# Dev_BRD_STM32F103C8T6.net
KiCad netlist of a schematic drawn in Altium Designer
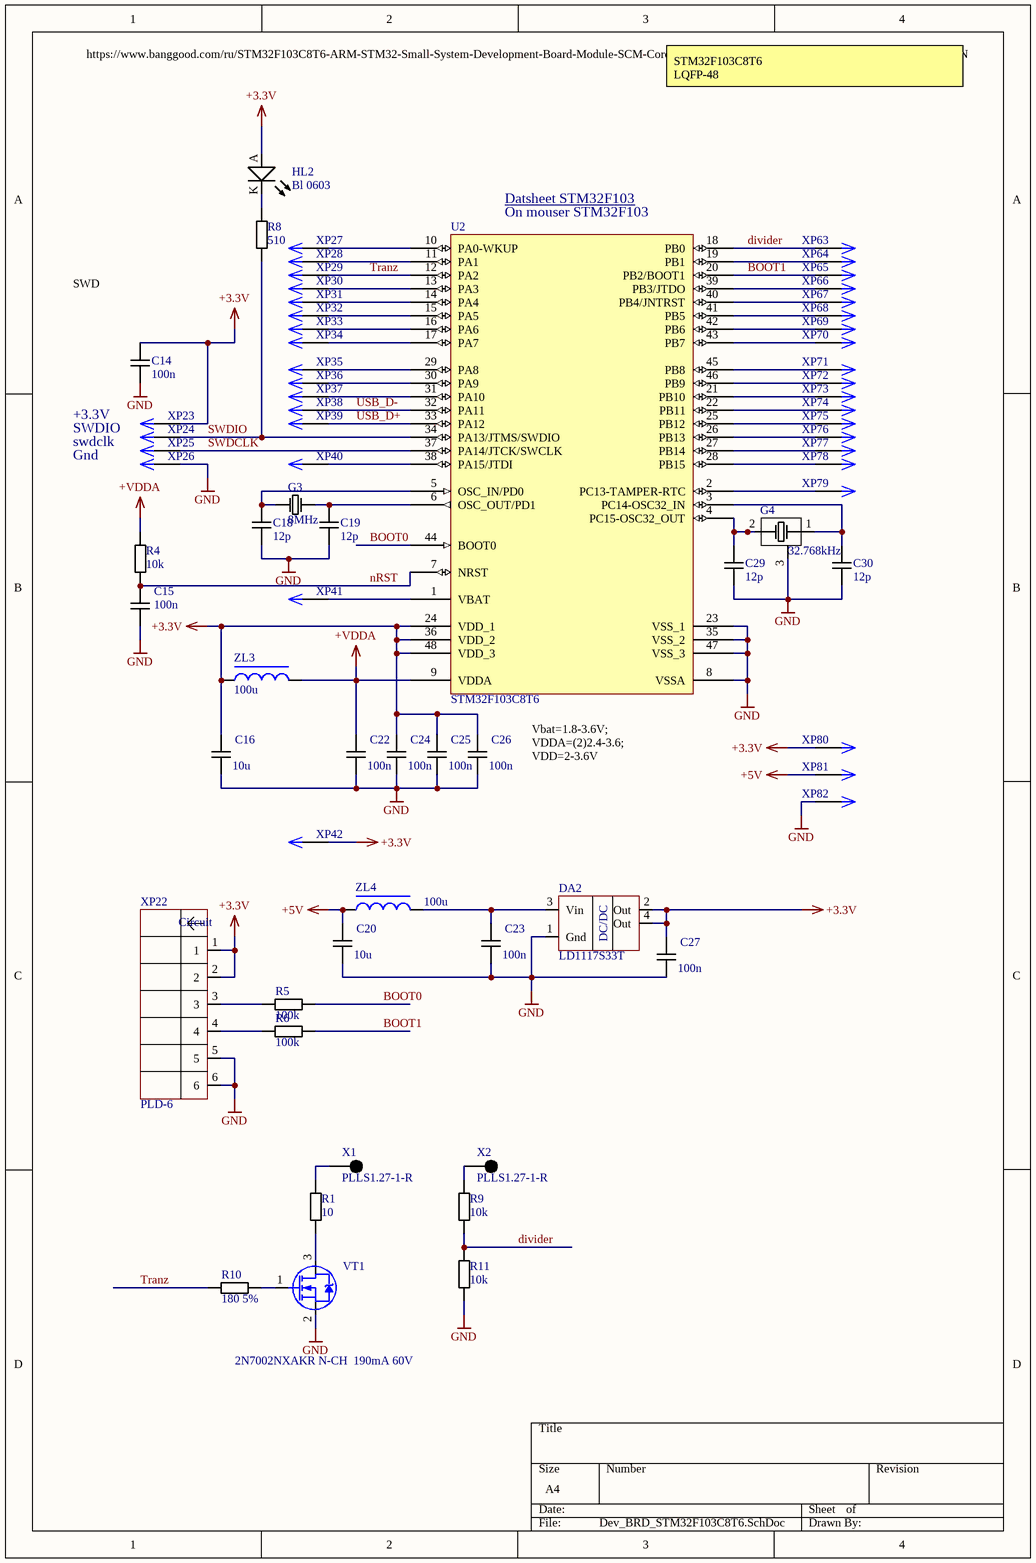
[diagram p0: Dev_BRD_STM32F103C8T6.SchDoc]

(export (version "E")
  (design (tool "Eeschema 10.0.6"))
  (components
    (comp (ref "C14")
      (value "100n")
      (footprint "CAPC1608(0603)N")
      (description "?")
      (fields (field (name "PART NUMBER") "CAPC1608(0603)"))
      (libsource (lib "SssAccesDatbase") (part "Cap"))
    )
    (comp (ref "C15")
      (value "100n")
      (footprint "CAPC1608(0603)N")
      (description "?")
      (fields (field (name "PART NUMBER") "CAPC1608(0603)"))
      (libsource (lib "SssAccesDatbase") (part "Cap"))
    )
    (comp (ref "C16")
      (value "10u")
      (footprint "CAPC1608(0603)N")
      (description "?")
      (fields (field (name "PART NUMBER") "CAPC1608(0603)"))
      (libsource (lib "SssAccesDatbase") (part "Cap"))
    )
    (comp (ref "C18")
      (value "12p")
      (footprint "CAPC1608(0603)N")
      (description "?")
      (fields (field (name "PART NUMBER") "CAPC1608(0603)"))
      (libsource (lib "SssAccesDatbase") (part "Cap"))
    )
    (comp (ref "C19")
      (value "12p")
      (footprint "CAPC1608(0603)N")
      (description "?")
      (fields (field (name "PART NUMBER") "CAPC1608(0603)"))
      (libsource (lib "SssAccesDatbase") (part "Cap"))
    )
    (comp (ref "C20")
      (value "10u")
      (footprint "CAPC1608(0603)N")
      (description "?")
      (fields (field (name "PART NUMBER") "CAPC1608(0603)"))
      (libsource (lib "SssAccesDatbase") (part "Cap"))
    )
    (comp (ref "C22")
      (value "100n")
      (footprint "CAPC1608(0603)N")
      (description "?")
      (fields (field (name "PART NUMBER") "CAPC1608(0603)"))
      (libsource (lib "SssAccesDatbase") (part "Cap"))
    )
    (comp (ref "C23")
      (value "100n")
      (footprint "CAPC1608(0603)N")
      (description "?")
      (fields (field (name "PART NUMBER") "CAPC1608(0603)"))
      (libsource (lib "SssAccesDatbase") (part "Cap"))
    )
    (comp (ref "C24")
      (value "100n")
      (footprint "CAPC1608(0603)N")
      (description "?")
      (fields (field (name "PART NUMBER") "CAPC1608(0603)"))
      (libsource (lib "SssAccesDatbase") (part "Cap"))
    )
    (comp (ref "C25")
      (value "100n")
      (footprint "CAPC1608(0603)N")
      (description "?")
      (fields (field (name "PART NUMBER") "CAPC1608(0603)"))
      (libsource (lib "SssAccesDatbase") (part "Cap"))
    )
    (comp (ref "C26")
      (value "100n")
      (footprint "CAPC1608(0603)N")
      (description "?")
      (fields (field (name "PART NUMBER") "CAPC1608(0603)"))
      (libsource (lib "SssAccesDatbase") (part "Cap"))
    )
    (comp (ref "C27")
      (value "100n")
      (footprint "CAPC1608(0603)N")
      (description "?")
      (fields (field (name "PART NUMBER") "CAPC1608(0603)"))
      (libsource (lib "SssAccesDatbase") (part "Cap"))
    )
    (comp (ref "C29")
      (value "12p")
      (footprint "CAPC1608(0603)N")
      (description "?")
      (fields (field (name "PART NUMBER") "CAPC1608(0603)"))
      (libsource (lib "SssAccesDatbase") (part "Cap"))
    )
    (comp (ref "C30")
      (value "12p")
      (footprint "CAPC1608(0603)N")
      (description "?")
      (fields (field (name "PART NUMBER") "CAPC1608(0603)"))
      (libsource (lib "SssAccesDatbase") (part "Cap"))
    )
    (comp (ref "DA2")
      (value "LD1117S33T")
      (footprint "SOT223_M")
      (description "LDO Voltage Regulators 3.3V 0.8A Positive")
      (fields (field (name "DIGI-KEY PART NUMBER") "?"))
      (libsource (lib "SssAccesDatbase") (part "LD1117S33T"))
    )
    (comp (ref "G3")
      (value "8MHz")
      (footprint "HC-49/S")
      (description "Crystal HC-49/S")
      (libsource (lib "SssAccesDatbase") (part "Crystal"))
    )
    (comp (ref "G4")
      (value "32.768kHz")
      (footprint "CRYSTAL_CMR309T")
      (description "Crystals 32.768KHz")
      (fields
        (field (name "PART NUMBER") "AB26T-32.768KHZ")
        (field (name "MOUSER PART NUMBER") "815-AB26T-32.768KHZ")
      )
      (libsource (lib "SssAccesDatbase") (part "Crystal 3 pin"))
    )
    (comp (ref "HL2")
      (value "Bl 0603")
      (footprint "LED-0603-BLUE")
      (description "LED BLUE DIFFUSED 0603 SMD")
      (fields
        (field (name "PART NUMBER") "150060BS55040")
        (field (name "DIGI-KEY PART NUMBER") "732-12013-1-ND")
      )
      (libsource (lib "SssAccesDatbase") (part "LED"))
    )
    (comp (ref "R1")
      (value "10")
      (footprint "REZKemet 0402")
      (description "RES SMD 0402 180 5% 100ppm")
      (fields
        (field (name "PART NUMBER") "RMCF0402JT180R")
        (field (name "DIGI-KEY PART NUMBER") "RMCF0402JT180RCT-ND")
      )
      (libsource (lib "") (part "Resistor general_1"))
    )
    (comp (ref "R4")
      (value "10k")
      (footprint "RESC1608(0603)N")
      (fields (field (name "PART NUMBER") "RESC1608(0603)") (field (name "DIGI-KEY PART NUMBER") "???"))
      (libsource (lib "") (part "Resistor general_1"))
    )
    (comp (ref "R5")
      (value "100k")
      (footprint "RESC1608(0603)N")
      (fields (field (name "PART NUMBER") "RESC1608(0603)") (field (name "DIGI-KEY PART NUMBER") "???"))
      (libsource (lib "SssAccesDatbase") (part "Resistor general"))
    )
    (comp (ref "R6")
      (value "100k")
      (footprint "RESC1608(0603)N")
      (fields (field (name "PART NUMBER") "RESC1608(0603)") (field (name "DIGI-KEY PART NUMBER") "???"))
      (libsource (lib "SssAccesDatbase") (part "Resistor general"))
    )
    (comp (ref "R8")
      (value "510")
      (footprint "RESC1608(0603)N")
      (fields (field (name "PART NUMBER") "RESC1608(0603)") (field (name "DIGI-KEY PART NUMBER") "???"))
      (libsource (lib "") (part "Resistor general_3"))
    )
    (comp (ref "R9")
      (value "10k")
      (footprint "RESC1608(0603)N")
      (fields (field (name "PART NUMBER") "RESC1608(0603)") (field (name "DIGI-KEY PART NUMBER") "???"))
      (libsource (lib "") (part "Resistor general_1"))
    )
    (comp (ref "R10")
      (value "180 5%")
      (footprint "REZKemet 0402")
      (description "RES SMD 0402 180 5% 100ppm")
      (fields
        (field (name "PART NUMBER") "RMCF0402JT180R")
        (field (name "DIGI-KEY PART NUMBER") "RMCF0402JT180RCT-ND")
      )
      (libsource (lib "") (part "Resistor general_2"))
    )
    (comp (ref "R11")
      (value "10k")
      (footprint "RESC1608(0603)N")
      (fields (field (name "PART NUMBER") "RESC1608(0603)") (field (name "DIGI-KEY PART NUMBER") "???"))
      (libsource (lib "") (part "Resistor general_1"))
    )
    (comp (ref "U2")
      (value "STM32F103C8T6")
      (footprint "LQFP48_L")
      (description "ARM Microcontrollers - MCU 32BIT Cortex M3 64KB 20KB RAM 2X12 ADC")
      (fields
        (field (name "MOUSER PART NUMBER") "511-STM32F103C8T6")
        (field (name "PUBLISHER") "Altium Limited")
      )
      (libsource (lib "SssAccesDatbase") (part "STM32F103C8T6"))
    )
    (comp (ref "VT1")
      (value "2N7002NXAKR N-CH  190mА 60V")
      (footprint "SOT23-3N")
      (description "N-Channel 60V 190mA (Ta), 300mA (Tc) 265mW (Ta), 1.33W (Tc) Surface Mount TO-236AB")
      (fields
        (field (name "PART NUMBER") "2N7002NXAKR")
        (field (name "DIGI-KEY PART NUMBER") "1727-8643-1-ND")
      )
      (libsource (lib "SssAccesDatbase") (part "N-CH_MOSFET_GSD"))
    )
    (comp (ref "X1")
      (value "PLLS1.27-1-R")
      (footprint "PLLS1.27-1-R")
      (libsource (lib "SssAccesDatbase") (part "X1_1"))
    )
    (comp (ref "X2")
      (value "PLLS1.27-1-R")
      (footprint "PLLS1.27-1-R")
      (libsource (lib "SssAccesDatbase") (part "X1_1"))
    )
    (comp (ref "XP22")
      (value "PLD-6")
      (footprint "PLD-6-3D")
      (libsource (lib "SssAccesDatbase") (part "XP-6"))
    )
    (comp (ref "XP23")
      (value "PLS-1")
      (footprint "PLS-1-3D")
      (description "CONN HEADER VERT 1POS")
      (fields
        (field (name "DIGI-KEY PART NUMBER") "S1011EC-01-ND")
        (field (name "MANUFACTURER PART NUMBER") "PRPC001SAAN-RC")
      )
      (libsource (lib "SssAccesDatbase") (part "XP-1_1"))
    )
    (comp (ref "XP24")
      (value "PLS-1")
      (footprint "PLS-1-3D")
      (description "CONN HEADER VERT 1POS")
      (fields
        (field (name "DIGI-KEY PART NUMBER") "S1011EC-01-ND")
        (field (name "MANUFACTURER PART NUMBER") "PRPC001SAAN-RC")
      )
      (libsource (lib "SssAccesDatbase") (part "XP-1_1"))
    )
    (comp (ref "XP25")
      (value "PLS-1")
      (footprint "PLS-1-3D")
      (description "CONN HEADER VERT 1POS")
      (fields
        (field (name "DIGI-KEY PART NUMBER") "S1011EC-01-ND")
        (field (name "MANUFACTURER PART NUMBER") "PRPC001SAAN-RC")
      )
      (libsource (lib "SssAccesDatbase") (part "XP-1_1"))
    )
    (comp (ref "XP26")
      (value "PLS-1")
      (footprint "PLS-1-3D")
      (description "CONN HEADER VERT 1POS")
      (fields
        (field (name "DIGI-KEY PART NUMBER") "S1011EC-01-ND")
        (field (name "MANUFACTURER PART NUMBER") "PRPC001SAAN-RC")
      )
      (libsource (lib "SssAccesDatbase") (part "XP-1_1"))
    )
    (comp (ref "XP27")
      (value "PLS-1")
      (footprint "PLS-1-3D")
      (description "CONN HEADER VERT 1POS")
      (fields
        (field (name "DIGI-KEY PART NUMBER") "S1011EC-01-ND")
        (field (name "MANUFACTURER PART NUMBER") "PRPC001SAAN-RC")
      )
      (libsource (lib "SssAccesDatbase") (part "XP-1_1"))
    )
    (comp (ref "XP28")
      (value "PLS-1")
      (footprint "PLS-1-3D")
      (description "CONN HEADER VERT 1POS")
      (fields
        (field (name "DIGI-KEY PART NUMBER") "S1011EC-01-ND")
        (field (name "MANUFACTURER PART NUMBER") "PRPC001SAAN-RC")
      )
      (libsource (lib "SssAccesDatbase") (part "XP-1_1"))
    )
    (comp (ref "XP29")
      (value "PLS-1")
      (footprint "PLS-1-3D")
      (description "CONN HEADER VERT 1POS")
      (fields
        (field (name "DIGI-KEY PART NUMBER") "S1011EC-01-ND")
        (field (name "MANUFACTURER PART NUMBER") "PRPC001SAAN-RC")
      )
      (libsource (lib "SssAccesDatbase") (part "XP-1_1"))
    )
    (comp (ref "XP30")
      (value "PLS-1")
      (footprint "PLS-1-3D")
      (description "CONN HEADER VERT 1POS")
      (fields
        (field (name "DIGI-KEY PART NUMBER") "S1011EC-01-ND")
        (field (name "MANUFACTURER PART NUMBER") "PRPC001SAAN-RC")
      )
      (libsource (lib "SssAccesDatbase") (part "XP-1_1"))
    )
    (comp (ref "XP31")
      (value "PLS-1")
      (footprint "PLS-1-3D")
      (description "CONN HEADER VERT 1POS")
      (fields
        (field (name "DIGI-KEY PART NUMBER") "S1011EC-01-ND")
        (field (name "MANUFACTURER PART NUMBER") "PRPC001SAAN-RC")
      )
      (libsource (lib "SssAccesDatbase") (part "XP-1_1"))
    )
    (comp (ref "XP32")
      (value "PLS-1")
      (footprint "PLS-1-3D")
      (description "CONN HEADER VERT 1POS")
      (fields
        (field (name "DIGI-KEY PART NUMBER") "S1011EC-01-ND")
        (field (name "MANUFACTURER PART NUMBER") "PRPC001SAAN-RC")
      )
      (libsource (lib "SssAccesDatbase") (part "XP-1_1"))
    )
    (comp (ref "XP33")
      (value "PLS-1")
      (footprint "PLS-1-3D")
      (description "CONN HEADER VERT 1POS")
      (fields
        (field (name "DIGI-KEY PART NUMBER") "S1011EC-01-ND")
        (field (name "MANUFACTURER PART NUMBER") "PRPC001SAAN-RC")
      )
      (libsource (lib "SssAccesDatbase") (part "XP-1_1"))
    )
    (comp (ref "XP34")
      (value "PLS-1")
      (footprint "PLS-1-3D")
      (description "CONN HEADER VERT 1POS")
      (fields
        (field (name "DIGI-KEY PART NUMBER") "S1011EC-01-ND")
        (field (name "MANUFACTURER PART NUMBER") "PRPC001SAAN-RC")
      )
      (libsource (lib "SssAccesDatbase") (part "XP-1_1"))
    )
    (comp (ref "XP35")
      (value "PLS-1")
      (footprint "PLS-1-3D")
      (description "CONN HEADER VERT 1POS")
      (fields
        (field (name "DIGI-KEY PART NUMBER") "S1011EC-01-ND")
        (field (name "MANUFACTURER PART NUMBER") "PRPC001SAAN-RC")
      )
      (libsource (lib "SssAccesDatbase") (part "XP-1_1"))
    )
    (comp (ref "XP36")
      (value "PLS-1")
      (footprint "PLS-1-3D")
      (description "CONN HEADER VERT 1POS")
      (fields
        (field (name "DIGI-KEY PART NUMBER") "S1011EC-01-ND")
        (field (name "MANUFACTURER PART NUMBER") "PRPC001SAAN-RC")
      )
      (libsource (lib "SssAccesDatbase") (part "XP-1_1"))
    )
    (comp (ref "XP37")
      (value "PLS-1")
      (footprint "PLS-1-3D")
      (description "CONN HEADER VERT 1POS")
      (fields
        (field (name "DIGI-KEY PART NUMBER") "S1011EC-01-ND")
        (field (name "MANUFACTURER PART NUMBER") "PRPC001SAAN-RC")
      )
      (libsource (lib "SssAccesDatbase") (part "XP-1_1"))
    )
    (comp (ref "XP38")
      (value "PLS-1")
      (footprint "PLS-1-3D")
      (description "CONN HEADER VERT 1POS")
      (fields
        (field (name "DIGI-KEY PART NUMBER") "S1011EC-01-ND")
        (field (name "MANUFACTURER PART NUMBER") "PRPC001SAAN-RC")
      )
      (libsource (lib "SssAccesDatbase") (part "XP-1_1"))
    )
    (comp (ref "XP39")
      (value "PLS-1")
      (footprint "PLS-1-3D")
      (description "CONN HEADER VERT 1POS")
      (fields
        (field (name "DIGI-KEY PART NUMBER") "S1011EC-01-ND")
        (field (name "MANUFACTURER PART NUMBER") "PRPC001SAAN-RC")
      )
      (libsource (lib "SssAccesDatbase") (part "XP-1_1"))
    )
    (comp (ref "XP40")
      (value "PLS-1")
      (footprint "PLS-1-3D")
      (description "CONN HEADER VERT 1POS")
      (fields
        (field (name "DIGI-KEY PART NUMBER") "S1011EC-01-ND")
        (field (name "MANUFACTURER PART NUMBER") "PRPC001SAAN-RC")
      )
      (libsource (lib "SssAccesDatbase") (part "XP-1_1"))
    )
    (comp (ref "XP41")
      (value "PLS-1")
      (footprint "PLS-1-3D")
      (description "CONN HEADER VERT 1POS")
      (fields
        (field (name "DIGI-KEY PART NUMBER") "S1011EC-01-ND")
        (field (name "MANUFACTURER PART NUMBER") "PRPC001SAAN-RC")
      )
      (libsource (lib "SssAccesDatbase") (part "XP-1_1"))
    )
    (comp (ref "XP42")
      (value "PLS-1")
      (footprint "PLS-1-3D")
      (description "CONN HEADER VERT 1POS")
      (fields
        (field (name "DIGI-KEY PART NUMBER") "S1011EC-01-ND")
        (field (name "MANUFACTURER PART NUMBER") "PRPC001SAAN-RC")
      )
      (libsource (lib "SssAccesDatbase") (part "XP-1_1"))
    )
    (comp (ref "XP63")
      (value "PLS-1")
      (footprint "PLS-1-3D")
      (description "CONN HEADER VERT 1POS")
      (fields
        (field (name "DIGI-KEY PART NUMBER") "S1011EC-01-ND")
        (field (name "MANUFACTURER PART NUMBER") "PRPC001SAAN-RC")
      )
      (libsource (lib "SssAccesDatbase") (part "XP-1_1"))
    )
    (comp (ref "XP64")
      (value "PLS-1")
      (footprint "PLS-1-3D")
      (description "CONN HEADER VERT 1POS")
      (fields
        (field (name "DIGI-KEY PART NUMBER") "S1011EC-01-ND")
        (field (name "MANUFACTURER PART NUMBER") "PRPC001SAAN-RC")
      )
      (libsource (lib "SssAccesDatbase") (part "XP-1_1"))
    )
    (comp (ref "XP65")
      (value "PLS-1")
      (footprint "PLS-1-3D")
      (description "CONN HEADER VERT 1POS")
      (fields
        (field (name "DIGI-KEY PART NUMBER") "S1011EC-01-ND")
        (field (name "MANUFACTURER PART NUMBER") "PRPC001SAAN-RC")
      )
      (libsource (lib "SssAccesDatbase") (part "XP-1_1"))
    )
    (comp (ref "XP66")
      (value "PLS-1")
      (footprint "PLS-1-3D")
      (description "CONN HEADER VERT 1POS")
      (fields
        (field (name "DIGI-KEY PART NUMBER") "S1011EC-01-ND")
        (field (name "MANUFACTURER PART NUMBER") "PRPC001SAAN-RC")
      )
      (libsource (lib "SssAccesDatbase") (part "XP-1_1"))
    )
    (comp (ref "XP67")
      (value "PLS-1")
      (footprint "PLS-1-3D")
      (description "CONN HEADER VERT 1POS")
      (fields
        (field (name "DIGI-KEY PART NUMBER") "S1011EC-01-ND")
        (field (name "MANUFACTURER PART NUMBER") "PRPC001SAAN-RC")
      )
      (libsource (lib "SssAccesDatbase") (part "XP-1_1"))
    )
    (comp (ref "XP68")
      (value "PLS-1")
      (footprint "PLS-1-3D")
      (description "CONN HEADER VERT 1POS")
      (fields
        (field (name "DIGI-KEY PART NUMBER") "S1011EC-01-ND")
        (field (name "MANUFACTURER PART NUMBER") "PRPC001SAAN-RC")
      )
      (libsource (lib "SssAccesDatbase") (part "XP-1_1"))
    )
    (comp (ref "XP69")
      (value "PLS-1")
      (footprint "PLS-1-3D")
      (description "CONN HEADER VERT 1POS")
      (fields
        (field (name "DIGI-KEY PART NUMBER") "S1011EC-01-ND")
        (field (name "MANUFACTURER PART NUMBER") "PRPC001SAAN-RC")
      )
      (libsource (lib "SssAccesDatbase") (part "XP-1_1"))
    )
    (comp (ref "XP70")
      (value "PLS-1")
      (footprint "PLS-1-3D")
      (description "CONN HEADER VERT 1POS")
      (fields
        (field (name "DIGI-KEY PART NUMBER") "S1011EC-01-ND")
        (field (name "MANUFACTURER PART NUMBER") "PRPC001SAAN-RC")
      )
      (libsource (lib "SssAccesDatbase") (part "XP-1_1"))
    )
    (comp (ref "XP71")
      (value "PLS-1")
      (footprint "PLS-1-3D")
      (description "CONN HEADER VERT 1POS")
      (fields
        (field (name "DIGI-KEY PART NUMBER") "S1011EC-01-ND")
        (field (name "MANUFACTURER PART NUMBER") "PRPC001SAAN-RC")
      )
      (libsource (lib "SssAccesDatbase") (part "XP-1_1"))
    )
    (comp (ref "XP72")
      (value "PLS-1")
      (footprint "PLS-1-3D")
      (description "CONN HEADER VERT 1POS")
      (fields
        (field (name "DIGI-KEY PART NUMBER") "S1011EC-01-ND")
        (field (name "MANUFACTURER PART NUMBER") "PRPC001SAAN-RC")
      )
      (libsource (lib "SssAccesDatbase") (part "XP-1_1"))
    )
    (comp (ref "XP73")
      (value "PLS-1")
      (footprint "PLS-1-3D")
      (description "CONN HEADER VERT 1POS")
      (fields
        (field (name "DIGI-KEY PART NUMBER") "S1011EC-01-ND")
        (field (name "MANUFACTURER PART NUMBER") "PRPC001SAAN-RC")
      )
      (libsource (lib "SssAccesDatbase") (part "XP-1_1"))
    )
    (comp (ref "XP74")
      (value "PLS-1")
      (footprint "PLS-1-3D")
      (description "CONN HEADER VERT 1POS")
      (fields
        (field (name "DIGI-KEY PART NUMBER") "S1011EC-01-ND")
        (field (name "MANUFACTURER PART NUMBER") "PRPC001SAAN-RC")
      )
      (libsource (lib "SssAccesDatbase") (part "XP-1_1"))
    )
    (comp (ref "XP75")
      (value "PLS-1")
      (footprint "PLS-1-3D")
      (description "CONN HEADER VERT 1POS")
      (fields
        (field (name "DIGI-KEY PART NUMBER") "S1011EC-01-ND")
        (field (name "MANUFACTURER PART NUMBER") "PRPC001SAAN-RC")
      )
      (libsource (lib "SssAccesDatbase") (part "XP-1_1"))
    )
    (comp (ref "XP76")
      (value "PLS-1")
      (footprint "PLS-1-3D")
      (description "CONN HEADER VERT 1POS")
      (fields
        (field (name "DIGI-KEY PART NUMBER") "S1011EC-01-ND")
        (field (name "MANUFACTURER PART NUMBER") "PRPC001SAAN-RC")
      )
      (libsource (lib "SssAccesDatbase") (part "XP-1_1"))
    )
    (comp (ref "XP77")
      (value "PLS-1")
      (footprint "PLS-1-3D")
      (description "CONN HEADER VERT 1POS")
      (fields
        (field (name "DIGI-KEY PART NUMBER") "S1011EC-01-ND")
        (field (name "MANUFACTURER PART NUMBER") "PRPC001SAAN-RC")
      )
      (libsource (lib "SssAccesDatbase") (part "XP-1_1"))
    )
    (comp (ref "XP78")
      (value "PLS-1")
      (footprint "PLS-1-3D")
      (description "CONN HEADER VERT 1POS")
      (fields
        (field (name "DIGI-KEY PART NUMBER") "S1011EC-01-ND")
        (field (name "MANUFACTURER PART NUMBER") "PRPC001SAAN-RC")
      )
      (libsource (lib "SssAccesDatbase") (part "XP-1_1"))
    )
    (comp (ref "XP79")
      (value "PLS-1")
      (footprint "PLS-1-3D")
      (description "CONN HEADER VERT 1POS")
      (fields
        (field (name "DIGI-KEY PART NUMBER") "S1011EC-01-ND")
        (field (name "MANUFACTURER PART NUMBER") "PRPC001SAAN-RC")
      )
      (libsource (lib "SssAccesDatbase") (part "XP-1_1"))
    )
    (comp (ref "XP80")
      (value "PLS-1")
      (footprint "PLS-1-3D")
      (description "CONN HEADER VERT 1POS")
      (fields
        (field (name "DIGI-KEY PART NUMBER") "S1011EC-01-ND")
        (field (name "MANUFACTURER PART NUMBER") "PRPC001SAAN-RC")
      )
      (libsource (lib "SssAccesDatbase") (part "XP-1_1"))
    )
    (comp (ref "XP81")
      (value "PLS-1")
      (footprint "PLS-1-3D")
      (description "CONN HEADER VERT 1POS")
      (fields
        (field (name "DIGI-KEY PART NUMBER") "S1011EC-01-ND")
        (field (name "MANUFACTURER PART NUMBER") "PRPC001SAAN-RC")
      )
      (libsource (lib "SssAccesDatbase") (part "XP-1_1"))
    )
    (comp (ref "XP82")
      (value "PLS-1")
      (footprint "PLS-1-3D")
      (description "CONN HEADER VERT 1POS")
      (fields
        (field (name "DIGI-KEY PART NUMBER") "S1011EC-01-ND")
        (field (name "MANUFACTURER PART NUMBER") "PRPC001SAAN-RC")
      )
      (libsource (lib "SssAccesDatbase") (part "XP-1_1"))
    )
    (comp (ref "ZL3")
      (value "100u")
      (footprint "INDC1608(0603)N")
      (description "ferite bead")
      (fields (field (name "PART NUMBER") "Ferite1608(0603)") (field (name "DIGI-KEY PART NUMBER") "???"))
      (libsource (lib "SssAccesDatbase") (part "ZL"))
    )
    (comp (ref "ZL4")
      (value "100u")
      (footprint "INDC1608(0603)N")
      (description "ferite bead")
      (fields (field (name "PART NUMBER") "Ferite1608(0603)") (field (name "DIGI-KEY PART NUMBER") "???"))
      (libsource (lib "SssAccesDatbase") (part "ZL"))
    )
  )
  (nets
    (net (code "1") (name "+3.3V") (class "Default")
      (node (ref "C14") (pin "1") (pinfunction "1_1") (pintype "passive"))
      (node (ref "C16") (pin "2") (pinfunction "2_2") (pintype "passive"))
      (node (ref "C24") (pin "2") (pinfunction "2_2") (pintype "passive"))
      (node (ref "C25") (pin "2") (pinfunction "2_2") (pintype "passive"))
      (node (ref "C26") (pin "2") (pinfunction "2_2") (pintype "passive"))
      (node (ref "C27") (pin "2") (pinfunction "2_2") (pintype "passive"))
      (node (ref "DA2") (pin "2") (pinfunction "Out_2") (pintype "passive"))
      (node (ref "DA2") (pin "4") (pinfunction "Out_4") (pintype "passive"))
      (node (ref "HL2") (pin "A") (pinfunction "A_A") (pintype "passive"))
      (node (ref "U2") (pin "24") (pinfunction "VDD_1_24") (pintype "power_in"))
      (node (ref "U2") (pin "36") (pinfunction "VDD_2_36") (pintype "power_in"))
      (node (ref "U2") (pin "48") (pinfunction "VDD_3_48") (pintype "power_in"))
      (node (ref "XP22") (pin "1") (pinfunction "1_1") (pintype "passive"))
      (node (ref "XP22") (pin "2") (pinfunction "2_2") (pintype "passive"))
      (node (ref "XP23") (pin "1") (pinfunction "1_1") (pintype "passive"))
      (node (ref "XP42") (pin "1") (pinfunction "1_1") (pintype "passive"))
      (node (ref "XP80") (pin "1") (pinfunction "1_1") (pintype "passive"))
      (node (ref "ZL3") (pin "1") (pinfunction "1_1") (pintype "passive"))
    )
    (net (code "2") (name "+5V") (class "Default")
      (node (ref "C20") (pin "2") (pinfunction "2_2") (pintype "passive"))
      (node (ref "XP81") (pin "1") (pinfunction "1_1") (pintype "passive"))
      (node (ref "ZL4") (pin "1") (pinfunction "1_1") (pintype "passive"))
    )
    (net (code "3") (name "+VDDA") (class "Default")
      (node (ref "C22") (pin "2") (pinfunction "2_2") (pintype "passive"))
      (node (ref "R4") (pin "2") (pinfunction "2_2") (pintype "passive"))
      (node (ref "U2") (pin "9") (pinfunction "VDDA_9") (pintype "power_in"))
      (node (ref "ZL3") (pin "2") (pinfunction "2_2") (pintype "passive"))
    )
    (net (code "4") (name "/BOOT0") (class "Default")
      (node (ref "R5") (pin "1") (pinfunction "1_1") (pintype "passive"))
      (node (ref "U2") (pin "44") (pinfunction "BOOT0_44") (pintype "input"))
    )
    (net (code "5") (name "/BOOT1") (class "Default")
      (node (ref "R6") (pin "1") (pinfunction "1_1") (pintype "passive"))
      (node (ref "U2") (pin "20") (pinfunction "PB2/BOOT1_20") (pintype "bidirectional"))
      (node (ref "XP65") (pin "1") (pinfunction "1_1") (pintype "passive"))
    )
    (net (code "6") (name "/SWDCLK") (class "Default")
      (node (ref "U2") (pin "37") (pinfunction "PA14/JTCK/SWCLK_37") (pintype "bidirectional"))
      (node (ref "XP25") (pin "1") (pinfunction "1_1") (pintype "passive"))
    )
    (net (code "7") (name "/SWDIO") (class "Default")
      (node (ref "R8") (pin "2") (pinfunction "2_2") (pintype "passive"))
      (node (ref "U2") (pin "34") (pinfunction "PA13/JTMS/SWDIO_34") (pintype "bidirectional"))
      (node (ref "XP24") (pin "1") (pinfunction "1_1") (pintype "passive"))
    )
    (net (code "8") (name "/Tranz") (class "Default")
      (node (ref "R10") (pin "1") (pinfunction "1_1") (pintype "passive"))
      (node (ref "U2") (pin "12") (pinfunction "PA2_12") (pintype "bidirectional"))
      (node (ref "XP29") (pin "1") (pinfunction "1_1") (pintype "passive"))
    )
    (net (code "9") (name "/USB_D+") (class "Default")
      (node (ref "U2") (pin "33") (pinfunction "PA12_33") (pintype "bidirectional"))
      (node (ref "XP39") (pin "1") (pinfunction "1_1") (pintype "passive"))
    )
    (net (code "10") (name "/USB_D-") (class "Default")
      (node (ref "U2") (pin "32") (pinfunction "PA11_32") (pintype "bidirectional"))
      (node (ref "XP38") (pin "1") (pinfunction "1_1") (pintype "passive"))
    )
    (net (code "11") (name "/divider") (class "Default")
      (node (ref "R11") (pin "2") (pinfunction "2_2") (pintype "passive"))
      (node (ref "R9") (pin "1") (pinfunction "1_1") (pintype "passive"))
      (node (ref "U2") (pin "18") (pinfunction "PB0_18") (pintype "bidirectional"))
      (node (ref "XP63") (pin "1") (pinfunction "1_1") (pintype "passive"))
    )
    (net (code "12") (name "/nRST") (class "Default")
      (node (ref "C15") (pin "2") (pinfunction "2_2") (pintype "passive"))
      (node (ref "R4") (pin "1") (pinfunction "1_1") (pintype "passive"))
      (node (ref "U2") (pin "7") (pinfunction "NRST_7") (pintype "bidirectional"))
    )
    (net (code "13") (name "GND") (class "Default")
      (node (ref "C14") (pin "2") (pinfunction "2_2") (pintype "passive"))
      (node (ref "C15") (pin "1") (pinfunction "1_1") (pintype "passive"))
      (node (ref "C16") (pin "1") (pinfunction "1_1") (pintype "passive"))
      (node (ref "C18") (pin "1") (pinfunction "1_1") (pintype "passive"))
      (node (ref "C19") (pin "1") (pinfunction "1_1") (pintype "passive"))
      (node (ref "C20") (pin "1") (pinfunction "1_1") (pintype "passive"))
      (node (ref "C22") (pin "1") (pinfunction "1_1") (pintype "passive"))
      (node (ref "C23") (pin "1") (pinfunction "1_1") (pintype "passive"))
      (node (ref "C24") (pin "1") (pinfunction "1_1") (pintype "passive"))
      (node (ref "C25") (pin "1") (pinfunction "1_1") (pintype "passive"))
      (node (ref "C26") (pin "1") (pinfunction "1_1") (pintype "passive"))
      (node (ref "C27") (pin "1") (pinfunction "1_1") (pintype "passive"))
      (node (ref "C29") (pin "1") (pinfunction "1_1") (pintype "passive"))
      (node (ref "C30") (pin "1") (pinfunction "1_1") (pintype "passive"))
      (node (ref "DA2") (pin "1") (pinfunction "Gnd_1") (pintype "passive"))
      (node (ref "G4") (pin "3") (pinfunction "3_3") (pintype "passive"))
      (node (ref "R11") (pin "1") (pinfunction "1_1") (pintype "passive"))
      (node (ref "U2") (pin "23") (pinfunction "VSS_1_23") (pintype "power_in"))
      (node (ref "U2") (pin "35") (pinfunction "VSS_2_35") (pintype "power_in"))
      (node (ref "U2") (pin "47") (pinfunction "VSS_3_47") (pintype "power_in"))
      (node (ref "U2") (pin "8") (pinfunction "VSSA_8") (pintype "power_in"))
      (node (ref "VT1") (pin "2") (pinfunction "S_2") (pintype "passive"))
      (node (ref "XP22") (pin "5") (pinfunction "5_5") (pintype "passive"))
      (node (ref "XP22") (pin "6") (pinfunction "6_6") (pintype "passive"))
      (node (ref "XP26") (pin "1") (pinfunction "1_1") (pintype "passive"))
      (node (ref "XP82") (pin "1") (pinfunction "1_1") (pintype "passive"))
    )
    (net (code "14") (name "Net-(DA2-Vin)") (class "Default")
      (node (ref "C23") (pin "2") (pinfunction "2_2") (pintype "passive"))
      (node (ref "DA2") (pin "3") (pinfunction "Vin_3") (pintype "passive"))
      (node (ref "ZL4") (pin "2") (pinfunction "2_2") (pintype "passive"))
    )
    (net (code "15") (name "Net-(HL2-PadK)") (class "Default")
      (node (ref "HL2") (pin "K") (pinfunction "K_K") (pintype "passive"))
      (node (ref "R8") (pin "1") (pinfunction "1_1") (pintype "passive"))
    )
    (net (code "16") (name "Net-(R1-Pad2)") (class "Default")
      (node (ref "R1") (pin "2") (pinfunction "2_2") (pintype "passive"))
      (node (ref "X1") (pin "1") (pinfunction "1_1") (pintype "passive"))
    )
    (net (code "17") (name "Net-(R5-Pad2)") (class "Default")
      (node (ref "R5") (pin "2") (pinfunction "2_2") (pintype "passive"))
      (node (ref "XP22") (pin "3") (pinfunction "3_3") (pintype "passive"))
    )
    (net (code "18") (name "Net-(R6-Pad2)") (class "Default")
      (node (ref "R6") (pin "2") (pinfunction "2_2") (pintype "passive"))
      (node (ref "XP22") (pin "4") (pinfunction "4_4") (pintype "passive"))
    )
    (net (code "19") (name "Net-(R9-Pad2)") (class "Default")
      (node (ref "R9") (pin "2") (pinfunction "2_2") (pintype "passive"))
      (node (ref "X2") (pin "1") (pinfunction "1_1") (pintype "passive"))
    )
    (net (code "20") (name "Net-(U2-OSC_IN{slash}PD0)") (class "Default")
      (node (ref "C18") (pin "2") (pinfunction "2_2") (pintype "passive"))
      (node (ref "G3") (pin "1") (pinfunction "1_1") (pintype "passive"))
      (node (ref "U2") (pin "5") (pinfunction "OSC_IN/PD0_5") (pintype "input"))
    )
    (net (code "21") (name "Net-(U2-OSC_OUT{slash}PD1)") (class "Default")
      (node (ref "C19") (pin "2") (pinfunction "2_2") (pintype "passive"))
      (node (ref "G3") (pin "2") (pinfunction "2_2") (pintype "passive"))
      (node (ref "U2") (pin "6") (pinfunction "OSC_OUT/PD1_6") (pintype "output"))
    )
    (net (code "22") (name "Net-(U2-PA0-WKUP)") (class "Default")
      (node (ref "U2") (pin "10") (pinfunction "PA0-WKUP_10") (pintype "bidirectional"))
      (node (ref "XP27") (pin "1") (pinfunction "1_1") (pintype "passive"))
    )
    (net (code "23") (name "Net-(U2-PA1)") (class "Default")
      (node (ref "U2") (pin "11") (pinfunction "PA1_11") (pintype "bidirectional"))
      (node (ref "XP28") (pin "1") (pinfunction "1_1") (pintype "passive"))
    )
    (net (code "24") (name "Net-(U2-PA3)") (class "Default")
      (node (ref "U2") (pin "13") (pinfunction "PA3_13") (pintype "bidirectional"))
      (node (ref "XP30") (pin "1") (pinfunction "1_1") (pintype "passive"))
    )
    (net (code "25") (name "Net-(U2-PA4)") (class "Default")
      (node (ref "U2") (pin "14") (pinfunction "PA4_14") (pintype "bidirectional"))
      (node (ref "XP31") (pin "1") (pinfunction "1_1") (pintype "passive"))
    )
    (net (code "26") (name "Net-(U2-PA5)") (class "Default")
      (node (ref "U2") (pin "15") (pinfunction "PA5_15") (pintype "bidirectional"))
      (node (ref "XP32") (pin "1") (pinfunction "1_1") (pintype "passive"))
    )
    (net (code "27") (name "Net-(U2-PA6)") (class "Default")
      (node (ref "U2") (pin "16") (pinfunction "PA6_16") (pintype "bidirectional"))
      (node (ref "XP33") (pin "1") (pinfunction "1_1") (pintype "passive"))
    )
    (net (code "28") (name "Net-(U2-PA7)") (class "Default")
      (node (ref "U2") (pin "17") (pinfunction "PA7_17") (pintype "bidirectional"))
      (node (ref "XP34") (pin "1") (pinfunction "1_1") (pintype "passive"))
    )
    (net (code "29") (name "Net-(U2-PA8)") (class "Default")
      (node (ref "U2") (pin "29") (pinfunction "PA8_29") (pintype "bidirectional"))
      (node (ref "XP35") (pin "1") (pinfunction "1_1") (pintype "passive"))
    )
    (net (code "30") (name "Net-(U2-PA9)") (class "Default")
      (node (ref "U2") (pin "30") (pinfunction "PA9_30") (pintype "bidirectional"))
      (node (ref "XP36") (pin "1") (pinfunction "1_1") (pintype "passive"))
    )
    (net (code "31") (name "Net-(U2-PA10)") (class "Default")
      (node (ref "U2") (pin "31") (pinfunction "PA10_31") (pintype "bidirectional"))
      (node (ref "XP37") (pin "1") (pinfunction "1_1") (pintype "passive"))
    )
    (net (code "32") (name "Net-(U2-PA15{slash}JTDI)") (class "Default")
      (node (ref "U2") (pin "38") (pinfunction "PA15/JTDI_38") (pintype "bidirectional"))
      (node (ref "XP40") (pin "1") (pinfunction "1_1") (pintype "passive"))
    )
    (net (code "33") (name "Net-(U2-PB1)") (class "Default")
      (node (ref "U2") (pin "19") (pinfunction "PB1_19") (pintype "bidirectional"))
      (node (ref "XP64") (pin "1") (pinfunction "1_1") (pintype "passive"))
    )
    (net (code "34") (name "Net-(U2-PB3{slash}JTDO)") (class "Default")
      (node (ref "U2") (pin "39") (pinfunction "PB3/JTDO_39") (pintype "bidirectional"))
      (node (ref "XP66") (pin "1") (pinfunction "1_1") (pintype "passive"))
    )
    (net (code "35") (name "Net-(U2-PB4{slash}JNTRST)") (class "Default")
      (node (ref "U2") (pin "40") (pinfunction "PB4/JNTRST_40") (pintype "bidirectional"))
      (node (ref "XP67") (pin "1") (pinfunction "1_1") (pintype "passive"))
    )
    (net (code "36") (name "Net-(U2-PB5)") (class "Default")
      (node (ref "U2") (pin "41") (pinfunction "PB5_41") (pintype "bidirectional"))
      (node (ref "XP68") (pin "1") (pinfunction "1_1") (pintype "passive"))
    )
    (net (code "37") (name "Net-(U2-PB6)") (class "Default")
      (node (ref "U2") (pin "42") (pinfunction "PB6_42") (pintype "bidirectional"))
      (node (ref "XP69") (pin "1") (pinfunction "1_1") (pintype "passive"))
    )
    (net (code "38") (name "Net-(U2-PB7)") (class "Default")
      (node (ref "U2") (pin "43") (pinfunction "PB7_43") (pintype "bidirectional"))
      (node (ref "XP70") (pin "1") (pinfunction "1_1") (pintype "passive"))
    )
    (net (code "39") (name "Net-(U2-PB8)") (class "Default")
      (node (ref "U2") (pin "45") (pinfunction "PB8_45") (pintype "bidirectional"))
      (node (ref "XP71") (pin "1") (pinfunction "1_1") (pintype "passive"))
    )
    (net (code "40") (name "Net-(U2-PB9)") (class "Default")
      (node (ref "U2") (pin "46") (pinfunction "PB9_46") (pintype "bidirectional"))
      (node (ref "XP72") (pin "1") (pinfunction "1_1") (pintype "passive"))
    )
    (net (code "41") (name "Net-(U2-PB10)") (class "Default")
      (node (ref "U2") (pin "21") (pinfunction "PB10_21") (pintype "bidirectional"))
      (node (ref "XP73") (pin "1") (pinfunction "1_1") (pintype "passive"))
    )
    (net (code "42") (name "Net-(U2-PB11)") (class "Default")
      (node (ref "U2") (pin "22") (pinfunction "PB11_22") (pintype "bidirectional"))
      (node (ref "XP74") (pin "1") (pinfunction "1_1") (pintype "passive"))
    )
    (net (code "43") (name "Net-(U2-PB12)") (class "Default")
      (node (ref "U2") (pin "25") (pinfunction "PB12_25") (pintype "bidirectional"))
      (node (ref "XP75") (pin "1") (pinfunction "1_1") (pintype "passive"))
    )
    (net (code "44") (name "Net-(U2-PB13)") (class "Default")
      (node (ref "U2") (pin "26") (pinfunction "PB13_26") (pintype "bidirectional"))
      (node (ref "XP76") (pin "1") (pinfunction "1_1") (pintype "passive"))
    )
    (net (code "45") (name "Net-(U2-PB14)") (class "Default")
      (node (ref "U2") (pin "27") (pinfunction "PB14_27") (pintype "bidirectional"))
      (node (ref "XP77") (pin "1") (pinfunction "1_1") (pintype "passive"))
    )
    (net (code "46") (name "Net-(U2-PB15)") (class "Default")
      (node (ref "U2") (pin "28") (pinfunction "PB15_28") (pintype "bidirectional"))
      (node (ref "XP78") (pin "1") (pinfunction "1_1") (pintype "passive"))
    )
    (net (code "47") (name "Net-(U2-PC13-TAMPER-RTC)") (class "Default")
      (node (ref "U2") (pin "2") (pinfunction "PC13-TAMPER-RTC_2") (pintype "bidirectional"))
      (node (ref "XP79") (pin "1") (pinfunction "1_1") (pintype "passive"))
    )
    (net (code "48") (name "Net-(U2-PC14-OSC32_IN)") (class "Default")
      (node (ref "C30") (pin "2") (pinfunction "2_2") (pintype "passive"))
      (node (ref "G4") (pin "1") (pinfunction "1_1") (pintype "passive"))
      (node (ref "U2") (pin "3") (pinfunction "PC14-OSC32_IN_3") (pintype "bidirectional"))
    )
    (net (code "49") (name "Net-(U2-PC15-OSC32_OUT)") (class "Default")
      (node (ref "C29") (pin "2") (pinfunction "2_2") (pintype "passive"))
      (node (ref "G4") (pin "2") (pinfunction "2_2") (pintype "passive"))
      (node (ref "U2") (pin "4") (pinfunction "PC15-OSC32_OUT_4") (pintype "bidirectional"))
    )
    (net (code "50") (name "Net-(U2-VBAT)") (class "Default")
      (node (ref "U2") (pin "1") (pinfunction "VBAT_1") (pintype "power_in"))
      (node (ref "XP41") (pin "1") (pinfunction "1_1") (pintype "passive"))
    )
    (net (code "51") (name "Net-(VT1-D)") (class "Default")
      (node (ref "R1") (pin "1") (pinfunction "1_1") (pintype "passive"))
      (node (ref "VT1") (pin "3") (pinfunction "D_3") (pintype "passive"))
    )
    (net (code "52") (name "Net-(VT1-G)") (class "Default")
      (node (ref "R10") (pin "2") (pinfunction "2_2") (pintype "passive"))
      (node (ref "VT1") (pin "1") (pinfunction "G_1") (pintype "passive"))
    )
  )
)
